# Pilot_Tone_-_Reference.net
KiCad netlist of a schematic drawn in Altium Designer
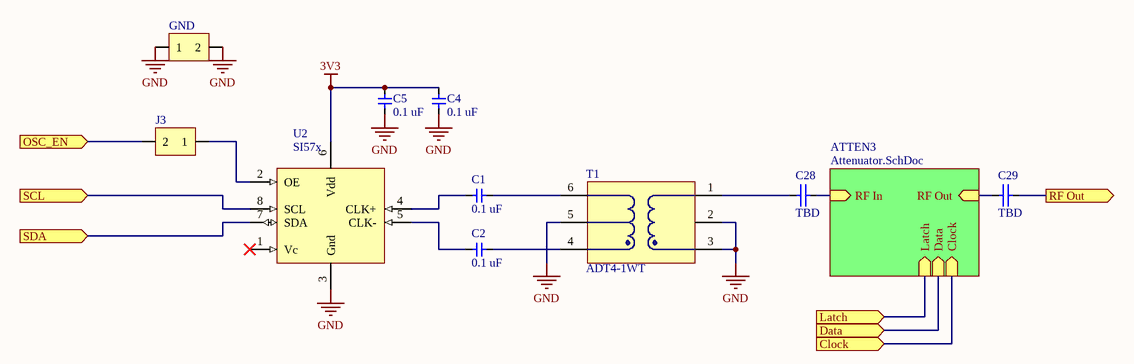
[diagram p0: Pilot Tone - Reference.SchDoc]

(export (version "E")
  (design (tool "Eeschema 10.0.6"))
  (components
    (comp (ref "C1")
      (value "0.1 uF")
      (footprint "0603C")
      (description "SMT Cap")
      (fields (field (name "PUBLISHER") "Altium Limited"))
      (libsource (lib "Miscellaneous Devices") (part "Cap - SMT Small"))
    )
    (comp (ref "C2")
      (value "0.1 uF")
      (footprint "0603C")
      (description "SMT Cap")
      (fields (field (name "PUBLISHER") "Altium Limited"))
      (libsource (lib "Miscellaneous Devices") (part "Cap - SMT Small"))
    )
    (comp (ref "C4")
      (value "0.1 uF")
      (footprint "0603C")
      (description "SMT Cap")
      (fields (field (name "PUBLISHER") "Altium Limited"))
      (libsource (lib "Miscellaneous Devices") (part "Cap - SMT Small"))
    )
    (comp (ref "C5")
      (value "0.1 uF")
      (footprint "0603C")
      (description "SMT Cap")
      (fields (field (name "PUBLISHER") "Altium Limited"))
      (libsource (lib "Miscellaneous Devices") (part "Cap - SMT Small"))
    )
    (comp (ref "C28")
      (value "TBD")
      (footprint "0402C")
      (description "Capacitor")
      (fields (field (name "Comment") "Cap") (field (name "PUBLISHER") "Altium Limited"))
      (libsource (lib "Miscellaneous Devices") (part "Cap"))
    )
    (comp (ref "C29")
      (value "TBD")
      (footprint "0402C")
      (description "Capacitor")
      (fields (field (name "Comment") "Cap") (field (name "PUBLISHER") "Altium Limited"))
      (libsource (lib "Miscellaneous Devices") (part "Cap"))
    )
    (comp (ref "GND")
      (value "Jumper")
      (footprint "HDR1X2")
      (description "Jumper - 2-Pin")
      (fields (field (name "PUBLISHER") "Altium Limited"))
      (libsource (lib "") (part "Jumper - 2 Pin_1"))
    )
    (comp (ref "J3")
      (value "Jumper")
      (footprint "0603R")
      (description "Jumper - 2-Pin")
      (fields (field (name "PUBLISHER") "Altium Limited"))
      (libsource (lib "Miscellaneous Connectors") (part "Jumper - 2 Pin"))
    )
    (comp (ref "T1")
      (value "ADT4-1WT")
      (footprint "CD542")
      (description "Surface Mount RF Transformer")
      (libsource (lib "RF Components") (part "ADT4-1WT"))
    )
    (comp (ref "U2")
      (value "SI57x")
      (footprint "SI57x")
      (description "10 MHZ TO 1.4 GHZ I2C PROGRAMMABLE XO/VCXO")
      (libsource (lib "RF Components") (part "SI570"))
    )
  )
  (nets
    (net (code "4") (name "/OSC_EN") (class "Default")
      (node (ref "J3") (pin "2") (pinfunction "2_2") (pintype "passive"))
    )
    (net (code "5") (name "/RF In") (class "Default")
      (node (ref "C28") (pin "2") (pinfunction "2_2") (pintype "passive"))
    )
    (net (code "6") (name "/RF Out") (class "Default")
      (node (ref "C29") (pin "2") (pinfunction "2_2") (pintype "passive"))
    )
    (net (code "7") (name "/RF Out_1") (class "Default")
      (node (ref "C29") (pin "1") (pinfunction "1_1") (pintype "passive"))
    )
    (net (code "8") (name "/SCL") (class "Default")
      (node (ref "U2") (pin "8") (pinfunction "SCL_8") (pintype "input"))
    )
    (net (code "9") (name "/SDA") (class "Default")
      (node (ref "U2") (pin "7") (pinfunction "SDA_7") (pintype "bidirectional"))
    )
    (net (code "10") (name "3V3") (class "Default")
      (node (ref "C4") (pin "2") (pinfunction "2_2") (pintype "passive"))
      (node (ref "C5") (pin "2") (pinfunction "2_2") (pintype "passive"))
      (node (ref "U2") (pin "6") (pinfunction "Vdd_6") (pintype "power_in"))
    )
    (net (code "11") (name "GND") (class "Default")
      (node (ref "C4") (pin "1") (pinfunction "1_1") (pintype "passive"))
      (node (ref "C5") (pin "1") (pinfunction "1_1") (pintype "passive"))
      (node (ref "GND") (pin "1") (pinfunction "1_1") (pintype "passive"))
      (node (ref "GND") (pin "2") (pinfunction "2_2") (pintype "passive"))
      (node (ref "T1") (pin "2") (pinfunction "Gnd_2") (pintype "power_in"))
      (node (ref "T1") (pin "3") (pinfunction "Coupled_3") (pintype "passive"))
      (node (ref "T1") (pin "5") (pinfunction "Termination_5") (pintype "passive"))
      (node (ref "U2") (pin "3") (pinfunction "Gnd_3") (pintype "power_in"))
    )
    (net (code "12") (name "Net-(C2-Pad2)") (class "Default")
      (node (ref "C2") (pin "2") (pinfunction "2_2") (pintype "passive"))
      (node (ref "T1") (pin "4") (pinfunction "Termination_4") (pintype "passive"))
    )
    (net (code "13") (name "Net-(T1-Input)") (class "Default")
      (node (ref "C28") (pin "1") (pinfunction "1_1") (pintype "passive"))
      (node (ref "T1") (pin "1") (pinfunction "Input_1") (pintype "passive"))
    )
    (net (code "14") (name "Net-(T1-Output)") (class "Default")
      (node (ref "C1") (pin "2") (pinfunction "2_2") (pintype "passive"))
      (node (ref "T1") (pin "6") (pinfunction "Output_6") (pintype "passive"))
    )
    (net (code "15") (name "Net-(U2-CLK+)") (class "Default")
      (node (ref "C1") (pin "1") (pinfunction "1_1") (pintype "passive"))
      (node (ref "U2") (pin "4") (pinfunction "CLK+_4") (pintype "input"))
    )
    (net (code "16") (name "Net-(U2-CLK-)") (class "Default")
      (node (ref "C2") (pin "1") (pinfunction "1_1") (pintype "passive"))
      (node (ref "U2") (pin "5") (pinfunction "CLK-_5") (pintype "input"))
    )
    (net (code "17") (name "Net-(U2-OE)") (class "Default")
      (node (ref "J3") (pin "1") (pinfunction "1_1") (pintype "passive"))
      (node (ref "U2") (pin "2") (pinfunction "OE_2") (pintype "input"))
    )
    (net (code "18") (name "unconnected-(U2-Vc-Pad1)") (class "Default")
      (node (ref "U2") (pin "1") (pinfunction "Vc_1") (pintype "input+no_connect"))
    )
  )
)
